# stm32-motor4.net
KiCad netlist of a schematic drawn in Altium Designer
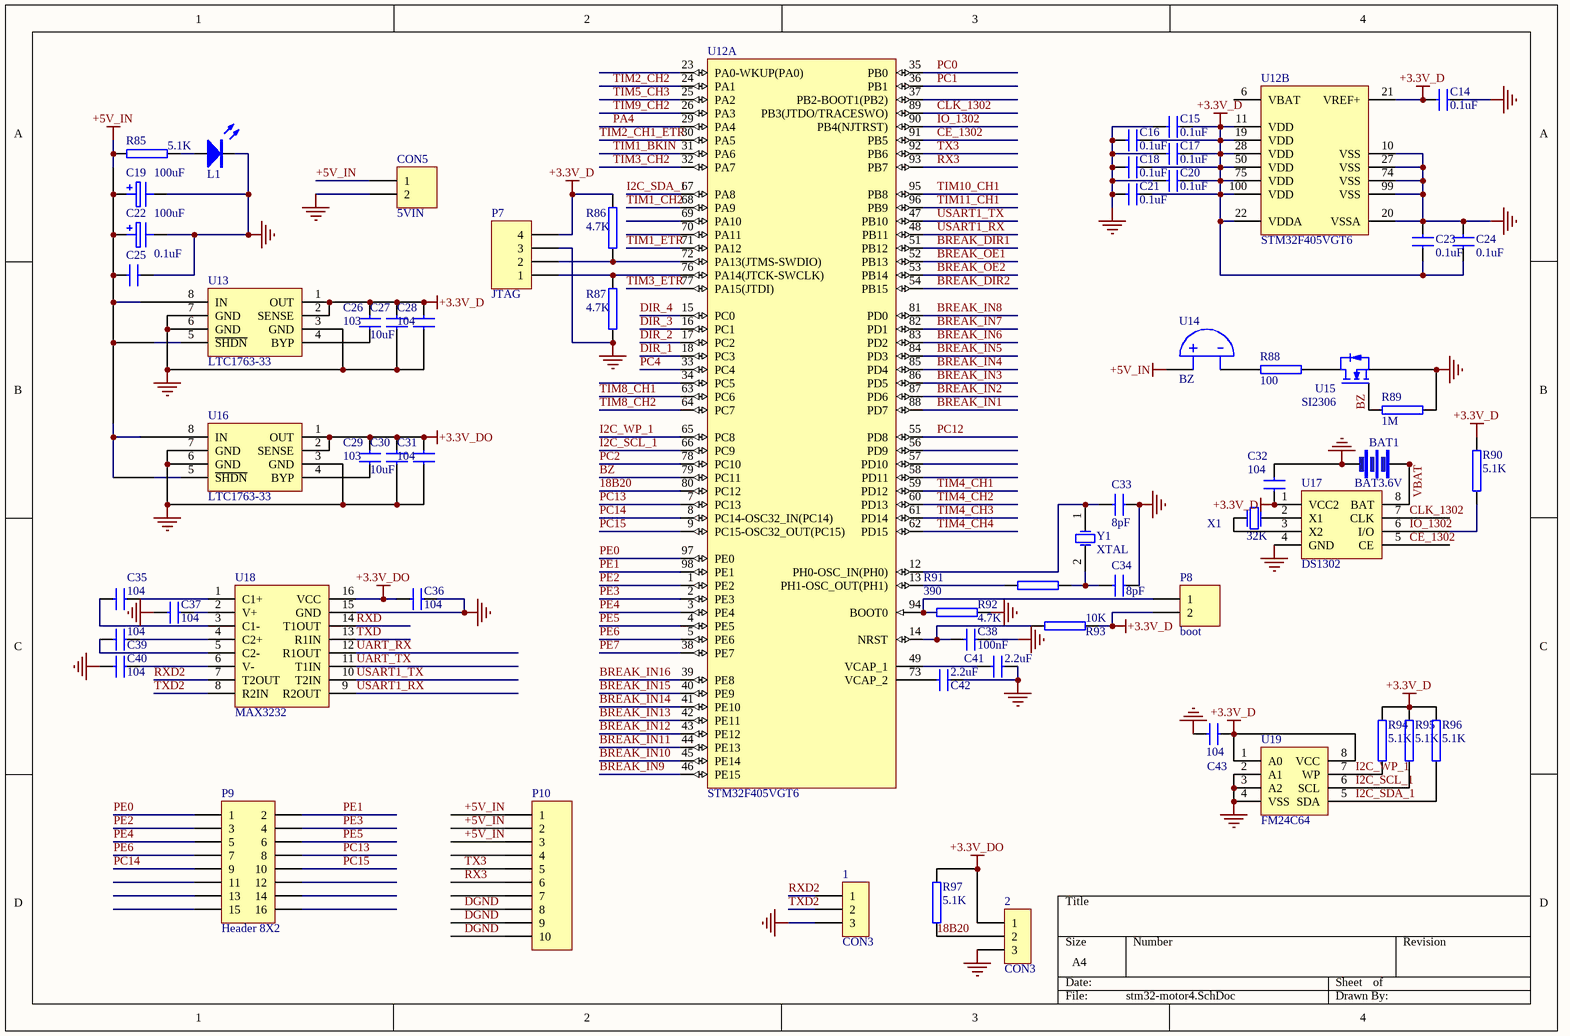
[diagram p0: stm32-motor4.SchDoc]

(export (version "E")
  (design (tool "Eeschema 10.0.6"))
  (components
    (comp (ref "1")
      (value "CON3")
      (footprint "SIP3")
      (description "Connector")
      (libsource (lib "插接件") (part "CON3"))
    )
    (comp (ref "2")
      (value "CON3")
      (footprint "SIP3")
      (description "Connector")
      (libsource (lib "插接件") (part "CON3"))
    )
    (comp (ref "BAT1") (value "BAT3.6V") (footprint "BAT") (libsource (lib "电池") (part "BAT3.6V")))
    (comp (ref "C14") (value "0.1uF") (footprint "0805") (libsource (lib "*") (part "C")))
    (comp (ref "C15") (value "0.1uF") (footprint "0805") (libsource (lib "*") (part "C")))
    (comp (ref "C16") (value "0.1uF") (footprint "0805") (libsource (lib "*") (part "C")))
    (comp (ref "C17") (value "0.1uF") (footprint "0805") (libsource (lib "*") (part "C")))
    (comp (ref "C18") (value "0.1uF") (footprint "0805") (libsource (lib "*") (part "C")))
    (comp (ref "C19") (value "100uF") (footprint "100UF/25V_CA") (libsource (lib "电容") (part "ELECTRO1")))
    (comp (ref "C20") (value "0.1uF") (footprint "0805") (libsource (lib "*") (part "C")))
    (comp (ref "C21") (value "0.1uF") (footprint "0805") (libsource (lib "*") (part "C")))
    (comp (ref "C22") (value "100uF") (footprint "100UF/25V_CA") (libsource (lib "电容") (part "ELECTRO1")))
    (comp (ref "C23") (value "0.1uF") (footprint "0805") (libsource (lib "*") (part "C")))
    (comp (ref "C24") (value "0.1uF") (footprint "0805") (libsource (lib "*") (part "C")))
    (comp (ref "C25") (value "0.1uF") (footprint "0805") (libsource (lib "电容") (part "C")))
    (comp (ref "C26") (value "103") (footprint "0603") (libsource (lib "电容") (part "C")))
    (comp (ref "C27") (value "10uF") (footprint "0805") (libsource (lib "电容") (part "C")))
    (comp (ref "C28") (value "104") (footprint "0805") (libsource (lib "电容") (part "C")))
    (comp (ref "C29") (value "103") (footprint "0603") (libsource (lib "电容") (part "C")))
    (comp (ref "C30") (value "10uF") (footprint "0805") (libsource (lib "电容") (part "C")))
    (comp (ref "C31") (value "104") (footprint "0805") (libsource (lib "电容") (part "C")))
    (comp (ref "C32") (value "104") (footprint "0805") (libsource (lib "电容") (part "C")))
    (comp (ref "C33") (value "8pF") (footprint "0805") (libsource (lib "*") (part "C")))
    (comp (ref "C34") (value "8pF") (footprint "0805") (libsource (lib "*") (part "C")))
    (comp (ref "C35") (value "104") (footprint "0805") (libsource (lib "*") (part "C")))
    (comp (ref "C36") (value "104") (footprint "0805") (libsource (lib "*") (part "C")))
    (comp (ref "C37") (value "104") (footprint "0805") (libsource (lib "*") (part "C")))
    (comp (ref "C38") (value "100nF") (footprint "0805") (libsource (lib "*") (part "C")))
    (comp (ref "C39") (value "104") (footprint "0805") (libsource (lib "*") (part "C")))
    (comp (ref "C40") (value "104") (footprint "0805") (libsource (lib "*") (part "C")))
    (comp (ref "C41") (value "2.2uF") (footprint "0805") (libsource (lib "*") (part "C")))
    (comp (ref "C42") (value "2.2uF") (footprint "0805") (libsource (lib "*") (part "C")))
    (comp (ref "C43") (value "104") (footprint "0805") (libsource (lib "电容") (part "C")))
    (comp (ref "CON5")
      (value "5VIN")
      (footprint "CON2")
      (description "Header, 2-Pin")
      (fields (field (name "PUBLISHER") "Altium Limited"))
      (libsource (lib "Miscellaneous Connectors") (part "Header 2"))
    )
    (comp (ref "L1") (value "LED") (footprint "0805LED") (libsource (lib "二极管") (part "LED")))
    (comp (ref "P7")
      (value "JTAG")
      (footprint "HDR1X4")
      (description "Header, 4-Pin")
      (fields (field (name "PUBLISHER") "Altium Limited"))
      (libsource (lib "Miscellaneous Connectors") (part "Header 4"))
    )
    (comp (ref "P8")
      (value "boot")
      (footprint "0603")
      (description "Header, 2-Pin")
      (fields (field (name "PUBLISHER") "Altium Limited"))
      (libsource (lib "Miscellaneous Connectors") (part "Header 2"))
    )
    (comp (ref "P9")
      (value "Header 8X2")
      (footprint "HDR2X8")
      (description "Header, 8-Pin, Dual row")
      (fields (field (name "PUBLISHER") "Altium Limited"))
      (libsource (lib "Miscellaneous Connectors") (part "Header 8X2"))
    )
    (comp (ref "P10")
      (value "ping")
      (footprint "PCBComponent_1")
      (description "Header, 10-Pin")
      (fields (field (name "PUBLISHER") "Altium Limited"))
      (libsource (lib "Miscellaneous Connectors") (part "Header 10"))
    )
    (comp (ref "R85") (value "5.1K") (footprint "0805") (libsource (lib "电阻") (part "RES")))
    (comp (ref "R86") (value "4.7K") (footprint "0805") (libsource (lib "*") (part "RES")))
    (comp (ref "R87") (value "4.7K") (footprint "0805") (libsource (lib "*") (part "RES")))
    (comp (ref "R88") (value "100") (footprint "0805") (libsource (lib "电阻") (part "RES")))
    (comp (ref "R89") (value "1M") (footprint "0805") (libsource (lib "电阻") (part "RES")))
    (comp (ref "R90") (value "5.1K") (footprint "0805") (libsource (lib "电阻") (part "RES")))
    (comp (ref "R91") (value "390") (footprint "0805") (libsource (lib "*") (part "RES")))
    (comp (ref "R92") (value "4.7K") (footprint "0805") (libsource (lib "*") (part "RES")))
    (comp (ref "R93") (value "10K") (footprint "0805") (libsource (lib "*") (part "RES")))
    (comp (ref "R94") (value "5.1K") (footprint "0805") (libsource (lib "电阻") (part "RES")))
    (comp (ref "R95") (value "5.1K") (footprint "0805") (libsource (lib "电阻") (part "RES")))
    (comp (ref "R96") (value "5.1K") (footprint "0805") (libsource (lib "电阻") (part "RES")))
    (comp (ref "R97") (value "5.1K") (footprint "0805") (libsource (lib "电阻") (part "RES")))
    (comp (ref "U12")
      (value "STM32F405VGT6")
      (footprint "STM-LQFP100_N")
      (fields (field (name "MANUFACTURER") "STMicroelectronics"))
      (libsource (lib "STMicroelectronics STM32 F4") (part "STM32F405VGT6"))
    )
    (comp (ref "U13") (value "LTC1763-33") (footprint "SO-8") (libsource (lib "单片机") (part "LT1763")))
    (comp (ref "U14") (value "BZ") (footprint "BZ_SMALL") (libsource (lib "蜂鸣器") (part "BZ")))
    (comp (ref "U15") (value "SI2306") (footprint "SOT-23") (libsource (lib "场效应管") (part "MOFET_N")))
    (comp (ref "U16") (value "LTC1763-33") (footprint "SO-8") (libsource (lib "单片机") (part "LT1763")))
    (comp (ref "U17") (value "DS1302") (footprint "SO-8") (libsource (lib "单片机") (part "DS1302")))
    (comp (ref "U18") (value "MAX3232") (footprint "SO-16") (libsource (lib "3D_GUASE") (part "MAX3232")))
    (comp (ref "U19") (value "FM24C64") (footprint "SO-8") (libsource (lib "单片机") (part "FM24C64")))
    (comp (ref "X1") (value "32K") (footprint "XTAL-2") (libsource (lib "晶振") (part "XTAL")))
    (comp (ref "Y1")
      (value "XTAL")
      (footprint "XTAL1")
      (description "Crystal Oscillator")
      (fields (field (name "PUBLISHER") "Altium Limited"))
      (libsource (lib "Miscellaneous Devices") (part "XTAL"))
    )
  )
  (nets
    (net (code "1") (name "+3.3V_D") (class "Default")
      (node (ref "C14") (pin "1") (pinfunction "1_1") (pintype "passive"))
      (node (ref "C15") (pin "2") (pinfunction "2_2") (pintype "passive"))
      (node (ref "C16") (pin "2") (pinfunction "2_2") (pintype "passive"))
      (node (ref "C17") (pin "2") (pinfunction "2_2") (pintype "passive"))
      (node (ref "C18") (pin "2") (pinfunction "2_2") (pintype "passive"))
      (node (ref "C20") (pin "2") (pinfunction "2_2") (pintype "passive"))
      (node (ref "C21") (pin "2") (pinfunction "2_2") (pintype "passive"))
      (node (ref "C23") (pin "2") (pinfunction "2_2") (pintype "passive"))
      (node (ref "C24") (pin "2") (pinfunction "2_2") (pintype "passive"))
      (node (ref "C26") (pin "1") (pinfunction "1_1") (pintype "passive"))
      (node (ref "C27") (pin "1") (pinfunction "1_1") (pintype "passive"))
      (node (ref "C28") (pin "1") (pinfunction "1_1") (pintype "passive"))
      (node (ref "C32") (pin "2") (pinfunction "2_2") (pintype "passive"))
      (node (ref "C43") (pin "1") (pinfunction "1_1") (pintype "passive"))
      (node (ref "P7") (pin "4") (pinfunction "4_4") (pintype "passive"))
      (node (ref "P8") (pin "2") (pinfunction "2_2") (pintype "passive"))
      (node (ref "R86") (pin "1") (pinfunction "1_1") (pintype "passive"))
      (node (ref "R90") (pin "2") (pinfunction "2_2") (pintype "passive"))
      (node (ref "R93") (pin "2") (pinfunction "2_2") (pintype "passive"))
      (node (ref "R94") (pin "2") (pinfunction "2_2") (pintype "passive"))
      (node (ref "R95") (pin "2") (pinfunction "2_2") (pintype "passive"))
      (node (ref "R96") (pin "2") (pinfunction "2_2") (pintype "passive"))
      (node (ref "U12") (pin "100") (pinfunction "VDD_100") (pintype "power_in"))
      (node (ref "U12") (pin "11") (pinfunction "VDD_11") (pintype "power_in"))
      (node (ref "U12") (pin "19") (pinfunction "VDD_19") (pintype "power_in"))
      (node (ref "U12") (pin "21") (pinfunction "VREF+_21") (pintype "power_in"))
      (node (ref "U12") (pin "22") (pinfunction "VDDA_22") (pintype "power_in"))
      (node (ref "U12") (pin "28") (pinfunction "VDD_28") (pintype "power_in"))
      (node (ref "U12") (pin "50") (pinfunction "VDD_50") (pintype "power_in"))
      (node (ref "U12") (pin "75") (pinfunction "VDD_75") (pintype "power_in"))
      (node (ref "U13") (pin "1") (pinfunction "OUT_1") (pintype "passive"))
      (node (ref "U13") (pin "2") (pinfunction "SENSE_2") (pintype "passive"))
      (node (ref "U17") (pin "1") (pinfunction "VCC2_1") (pintype "passive"))
      (node (ref "U19") (pin "1") (pinfunction "A0_1") (pintype "passive"))
      (node (ref "U19") (pin "8") (pinfunction "VCC_8") (pintype "passive"))
    )
    (net (code "2") (name "+3.3V_DO") (class "Default")
      (node (ref "2") (pin "1") (pinfunction "1_1") (pintype "passive"))
      (node (ref "C29") (pin "1") (pinfunction "1_1") (pintype "passive"))
      (node (ref "C30") (pin "1") (pinfunction "1_1") (pintype "passive"))
      (node (ref "C31") (pin "1") (pinfunction "1_1") (pintype "passive"))
      (node (ref "C36") (pin "1") (pinfunction "1_1") (pintype "passive"))
      (node (ref "R97") (pin "2") (pinfunction "2_2") (pintype "passive"))
      (node (ref "U16") (pin "1") (pinfunction "OUT_1") (pintype "passive"))
      (node (ref "U16") (pin "2") (pinfunction "SENSE_2") (pintype "passive"))
      (node (ref "U18") (pin "16") (pinfunction "VCC_16") (pintype "passive"))
    )
    (net (code "3") (name "+5V_IN") (class "Default")
      (node (ref "C19") (pin "1") (pintype "passive"))
      (node (ref "C22") (pin "1") (pintype "passive"))
      (node (ref "C25") (pin "1") (pinfunction "1_1") (pintype "passive"))
      (node (ref "CON5") (pin "1") (pinfunction "1_1") (pintype "passive"))
      (node (ref "P10") (pin "1") (pinfunction "1_1") (pintype "passive"))
      (node (ref "P10") (pin "2") (pinfunction "2_2") (pintype "passive"))
      (node (ref "P10") (pin "3") (pinfunction "3_3") (pintype "passive"))
      (node (ref "R85") (pin "2") (pinfunction "2_2") (pintype "passive"))
      (node (ref "U13") (pin "5") (pinfunction "~{SHDN}_5") (pintype "passive"))
      (node (ref "U13") (pin "8") (pinfunction "IN_8") (pintype "passive"))
      (node (ref "U14") (pin "1") (pintype "passive"))
      (node (ref "U16") (pin "5") (pinfunction "~{SHDN}_5") (pintype "passive"))
      (node (ref "U16") (pin "8") (pinfunction "IN_8") (pintype "passive"))
    )
    (net (code "4") (name "/18B20") (class "Default")
      (node (ref "2") (pin "2") (pinfunction "2_2") (pintype "passive"))
      (node (ref "R97") (pin "1") (pinfunction "1_1") (pintype "passive"))
      (node (ref "U12") (pin "80") (pinfunction "PC12_80") (pintype "bidirectional"))
    )
    (net (code "5") (name "/BREAK_DIR1") (class "Default")
      (node (ref "U12") (pin "51") (pinfunction "PB12_51") (pintype "bidirectional"))
    )
    (net (code "6") (name "/BREAK_DIR2") (class "Default")
      (node (ref "U12") (pin "54") (pinfunction "PB15_54") (pintype "bidirectional"))
    )
    (net (code "7") (name "/BREAK_IN1") (class "Default")
      (node (ref "U12") (pin "88") (pinfunction "PD7_88") (pintype "bidirectional"))
    )
    (net (code "8") (name "/BREAK_IN2") (class "Default")
      (node (ref "U12") (pin "87") (pinfunction "PD6_87") (pintype "bidirectional"))
    )
    (net (code "9") (name "/BREAK_IN3") (class "Default")
      (node (ref "U12") (pin "86") (pinfunction "PD5_86") (pintype "bidirectional"))
    )
    (net (code "10") (name "/BREAK_IN4") (class "Default")
      (node (ref "U12") (pin "85") (pinfunction "PD4_85") (pintype "bidirectional"))
    )
    (net (code "11") (name "/BREAK_IN5") (class "Default")
      (node (ref "U12") (pin "84") (pinfunction "PD3_84") (pintype "bidirectional"))
    )
    (net (code "12") (name "/BREAK_IN6") (class "Default")
      (node (ref "U12") (pin "83") (pinfunction "PD2_83") (pintype "bidirectional"))
    )
    (net (code "13") (name "/BREAK_IN7") (class "Default")
      (node (ref "U12") (pin "82") (pinfunction "PD1_82") (pintype "bidirectional"))
    )
    (net (code "14") (name "/BREAK_IN8") (class "Default")
      (node (ref "U12") (pin "81") (pinfunction "PD0_81") (pintype "bidirectional"))
    )
    (net (code "15") (name "/BREAK_IN9") (class "Default")
      (node (ref "U12") (pin "46") (pinfunction "PE15_46") (pintype "bidirectional"))
    )
    (net (code "16") (name "/BREAK_IN10") (class "Default")
      (node (ref "U12") (pin "45") (pinfunction "PE14_45") (pintype "bidirectional"))
    )
    (net (code "17") (name "/BREAK_IN11") (class "Default")
      (node (ref "U12") (pin "44") (pinfunction "PE13_44") (pintype "bidirectional"))
    )
    (net (code "18") (name "/BREAK_IN12") (class "Default")
      (node (ref "U12") (pin "43") (pinfunction "PE12_43") (pintype "bidirectional"))
    )
    (net (code "19") (name "/BREAK_IN13") (class "Default")
      (node (ref "U12") (pin "42") (pinfunction "PE11_42") (pintype "bidirectional"))
    )
    (net (code "20") (name "/BREAK_IN14") (class "Default")
      (node (ref "U12") (pin "41") (pinfunction "PE10_41") (pintype "bidirectional"))
    )
    (net (code "21") (name "/BREAK_IN15") (class "Default")
      (node (ref "U12") (pin "40") (pinfunction "PE9_40") (pintype "bidirectional"))
    )
    (net (code "22") (name "/BREAK_IN16") (class "Default")
      (node (ref "U12") (pin "39") (pinfunction "PE8_39") (pintype "bidirectional"))
    )
    (net (code "23") (name "/BREAK_OE1") (class "Default")
      (node (ref "U12") (pin "52") (pinfunction "PB13_52") (pintype "bidirectional"))
    )
    (net (code "24") (name "/BREAK_OE2") (class "Default")
      (node (ref "U12") (pin "53") (pinfunction "PB14_53") (pintype "bidirectional"))
    )
    (net (code "25") (name "/BZ") (class "Default")
      (node (ref "R89") (pin "2") (pinfunction "2_2") (pintype "passive"))
      (node (ref "U12") (pin "79") (pinfunction "PC11_79") (pintype "bidirectional"))
      (node (ref "U15") (pin "B") (pinfunction "B_B") (pintype "passive"))
    )
    (net (code "26") (name "/CE_1302") (class "Default")
      (node (ref "U12") (pin "91") (pinfunction "PB5_91") (pintype "bidirectional"))
      (node (ref "U17") (pin "5") (pinfunction "CE_5") (pintype "passive"))
    )
    (net (code "27") (name "/CLK_1302") (class "Default")
      (node (ref "U12") (pin "89") (pinfunction "PB3(JTDO/TRACESWO)_89") (pintype "bidirectional"))
      (node (ref "U17") (pin "7") (pinfunction "CLK_7") (pintype "passive"))
    )
    (net (code "28") (name "/DIR_1") (class "Default")
      (node (ref "U12") (pin "18") (pinfunction "PC3_18") (pintype "bidirectional"))
    )
    (net (code "29") (name "/DIR_2") (class "Default")
      (node (ref "U12") (pin "17") (pinfunction "PC2_17") (pintype "bidirectional"))
    )
    (net (code "30") (name "/DIR_3") (class "Default")
      (node (ref "U12") (pin "16") (pinfunction "PC1_16") (pintype "bidirectional"))
    )
    (net (code "31") (name "/DIR_4") (class "Default")
      (node (ref "U12") (pin "15") (pinfunction "PC0_15") (pintype "bidirectional"))
    )
    (net (code "32") (name "/I2C_SCL_1") (class "Default")
      (node (ref "R95") (pin "1") (pinfunction "1_1") (pintype "passive"))
      (node (ref "U12") (pin "66") (pinfunction "PC9_66") (pintype "bidirectional"))
      (node (ref "U19") (pin "6") (pinfunction "SCL_6") (pintype "passive"))
    )
    (net (code "33") (name "/I2C_SDA_1") (class "Default")
      (node (ref "R96") (pin "1") (pinfunction "1_1") (pintype "passive"))
      (node (ref "U12") (pin "67") (pinfunction "PA8_67") (pintype "bidirectional"))
      (node (ref "U19") (pin "5") (pinfunction "SDA_5") (pintype "passive"))
    )
    (net (code "34") (name "/I2C_WP_1") (class "Default")
      (node (ref "R94") (pin "1") (pinfunction "1_1") (pintype "passive"))
      (node (ref "U12") (pin "65") (pinfunction "PC8_65") (pintype "bidirectional"))
      (node (ref "U19") (pin "7") (pinfunction "WP_7") (pintype "passive"))
    )
    (net (code "35") (name "/IO_1302") (class "Default")
      (node (ref "R90") (pin "1") (pinfunction "1_1") (pintype "passive"))
      (node (ref "U12") (pin "90") (pinfunction "PB4(NJTRST)_90") (pintype "bidirectional"))
      (node (ref "U17") (pin "6") (pinfunction "I/O_6") (pintype "passive"))
    )
    (net (code "36") (name "/PA4") (class "Default")
      (node (ref "U12") (pin "29") (pinfunction "PA4_29") (pintype "bidirectional"))
    )
    (net (code "37") (name "/PC0") (class "Default")
      (node (ref "U12") (pin "35") (pinfunction "PB0_35") (pintype "bidirectional"))
    )
    (net (code "38") (name "/PC1") (class "Default")
      (node (ref "U12") (pin "36") (pinfunction "PB1_36") (pintype "bidirectional"))
    )
    (net (code "39") (name "/PC2") (class "Default")
      (node (ref "U12") (pin "78") (pinfunction "PC10_78") (pintype "bidirectional"))
    )
    (net (code "40") (name "/PC4") (class "Default")
      (node (ref "U12") (pin "33") (pinfunction "PC4_33") (pintype "bidirectional"))
    )
    (net (code "41") (name "/PC12") (class "Default")
      (node (ref "U12") (pin "55") (pinfunction "PD8_55") (pintype "bidirectional"))
    )
    (net (code "42") (name "/PC13") (class "Default")
      (node (ref "P9") (pin "8") (pinfunction "8_8") (pintype "passive"))
      (node (ref "U12") (pin "7") (pinfunction "PC13_7") (pintype "bidirectional"))
    )
    (net (code "43") (name "/PC14") (class "Default")
      (node (ref "P9") (pin "9") (pinfunction "9_9") (pintype "passive"))
      (node (ref "U12") (pin "8") (pinfunction "PC14-OSC32_IN(PC14)_8") (pintype "bidirectional"))
    )
    (net (code "44") (name "/PC15") (class "Default")
      (node (ref "P9") (pin "10") (pinfunction "10_10") (pintype "passive"))
      (node (ref "U12") (pin "9") (pinfunction "PC15-OSC32_OUT(PC15)_9") (pintype "bidirectional"))
    )
    (net (code "45") (name "/PE0") (class "Default")
      (node (ref "P9") (pin "1") (pinfunction "1_1") (pintype "passive"))
      (node (ref "U12") (pin "97") (pinfunction "PE0_97") (pintype "bidirectional"))
    )
    (net (code "46") (name "/PE1") (class "Default")
      (node (ref "P9") (pin "2") (pinfunction "2_2") (pintype "passive"))
      (node (ref "U12") (pin "98") (pinfunction "PE1_98") (pintype "bidirectional"))
    )
    (net (code "47") (name "/PE2") (class "Default")
      (node (ref "P9") (pin "3") (pinfunction "3_3") (pintype "passive"))
      (node (ref "U12") (pin "1") (pinfunction "PE2_1") (pintype "bidirectional"))
    )
    (net (code "48") (name "/PE3") (class "Default")
      (node (ref "P9") (pin "4") (pinfunction "4_4") (pintype "passive"))
      (node (ref "U12") (pin "2") (pinfunction "PE3_2") (pintype "bidirectional"))
    )
    (net (code "49") (name "/PE4") (class "Default")
      (node (ref "P9") (pin "5") (pinfunction "5_5") (pintype "passive"))
      (node (ref "U12") (pin "3") (pinfunction "PE4_3") (pintype "bidirectional"))
    )
    (net (code "50") (name "/PE5") (class "Default")
      (node (ref "P9") (pin "6") (pinfunction "6_6") (pintype "passive"))
      (node (ref "U12") (pin "4") (pinfunction "PE5_4") (pintype "bidirectional"))
    )
    (net (code "51") (name "/PE6") (class "Default")
      (node (ref "P9") (pin "7") (pinfunction "7_7") (pintype "passive"))
      (node (ref "U12") (pin "5") (pinfunction "PE6_5") (pintype "bidirectional"))
    )
    (net (code "52") (name "/PE7") (class "Default")
      (node (ref "U12") (pin "38") (pinfunction "PE7_38") (pintype "bidirectional"))
    )
    (net (code "53") (name "/RX3") (class "Default")
      (node (ref "P10") (pin "6") (pinfunction "6_6") (pintype "passive"))
      (node (ref "U12") (pin "93") (pinfunction "PB7_93") (pintype "bidirectional"))
    )
    (net (code "54") (name "/RXD") (class "Default")
      (node (ref "U18") (pin "14") (pinfunction "T1OUT_14") (pintype "passive"))
    )
    (net (code "55") (name "/RXD2") (class "Default")
      (node (ref "1") (pin "1") (pinfunction "1_1") (pintype "passive"))
      (node (ref "U18") (pin "7") (pinfunction "T2OUT_7") (pintype "passive"))
    )
    (net (code "56") (name "/TIM1_BKIN") (class "Default")
      (node (ref "U12") (pin "31") (pinfunction "PA6_31") (pintype "bidirectional"))
    )
    (net (code "57") (name "/TIM1_CH2") (class "Default")
      (node (ref "U12") (pin "68") (pinfunction "PA9_68") (pintype "bidirectional"))
    )
    (net (code "58") (name "/TIM1_ETR") (class "Default")
      (node (ref "U12") (pin "71") (pinfunction "PA12_71") (pintype "bidirectional"))
    )
    (net (code "59") (name "/TIM2_CH1_ETR") (class "Default")
      (node (ref "U12") (pin "30") (pinfunction "PA5_30") (pintype "bidirectional"))
    )
    (net (code "60") (name "/TIM2_CH2") (class "Default")
      (node (ref "U12") (pin "24") (pinfunction "PA1_24") (pintype "bidirectional"))
    )
    (net (code "61") (name "/TIM3_CH2") (class "Default")
      (node (ref "U12") (pin "32") (pinfunction "PA7_32") (pintype "bidirectional"))
    )
    (net (code "62") (name "/TIM3_ETR") (class "Default")
      (node (ref "U12") (pin "77") (pinfunction "PA15(JTDI)_77") (pintype "bidirectional"))
    )
    (net (code "63") (name "/TIM4_CH1") (class "Default")
      (node (ref "U12") (pin "59") (pinfunction "PD12_59") (pintype "bidirectional"))
    )
    (net (code "64") (name "/TIM4_CH2") (class "Default")
      (node (ref "U12") (pin "60") (pinfunction "PD13_60") (pintype "bidirectional"))
    )
    (net (code "65") (name "/TIM4_CH3") (class "Default")
      (node (ref "U12") (pin "61") (pinfunction "PD14_61") (pintype "bidirectional"))
    )
    (net (code "66") (name "/TIM4_CH4") (class "Default")
      (node (ref "U12") (pin "62") (pinfunction "PD15_62") (pintype "bidirectional"))
    )
    (net (code "67") (name "/TIM5_CH3") (class "Default")
      (node (ref "U12") (pin "25") (pinfunction "PA2_25") (pintype "bidirectional"))
    )
    (net (code "68") (name "/TIM8_CH1") (class "Default")
      (node (ref "U12") (pin "63") (pinfunction "PC6_63") (pintype "bidirectional"))
    )
    (net (code "69") (name "/TIM8_CH2") (class "Default")
      (node (ref "U12") (pin "64") (pinfunction "PC7_64") (pintype "bidirectional"))
    )
    (net (code "70") (name "/TIM9_CH2") (class "Default")
      (node (ref "U12") (pin "26") (pinfunction "PA3_26") (pintype "bidirectional"))
    )
    (net (code "71") (name "/TIM10_CH1") (class "Default")
      (node (ref "U12") (pin "95") (pinfunction "PB8_95") (pintype "bidirectional"))
    )
    (net (code "72") (name "/TIM11_CH1") (class "Default")
      (node (ref "U12") (pin "96") (pinfunction "PB9_96") (pintype "bidirectional"))
    )
    (net (code "73") (name "/TX3") (class "Default")
      (node (ref "P10") (pin "5") (pinfunction "5_5") (pintype "passive"))
      (node (ref "U12") (pin "92") (pinfunction "PB6_92") (pintype "bidirectional"))
    )
    (net (code "74") (name "/TXD") (class "Default")
      (node (ref "U18") (pin "13") (pinfunction "R1IN_13") (pintype "passive"))
    )
    (net (code "75") (name "/TXD2") (class "Default")
      (node (ref "1") (pin "2") (pinfunction "2_2") (pintype "passive"))
      (node (ref "U18") (pin "8") (pinfunction "R2IN_8") (pintype "passive"))
    )
    (net (code "76") (name "/UART_RX") (class "Default")
      (node (ref "U18") (pin "12") (pinfunction "R1OUT_12") (pintype "passive"))
    )
    (net (code "77") (name "/UART_TX") (class "Default")
      (node (ref "U18") (pin "11") (pinfunction "T1IN_11") (pintype "passive"))
    )
    (net (code "78") (name "/USART1_RX") (class "Default")
      (node (ref "U12") (pin "48") (pinfunction "PB11_48") (pintype "bidirectional"))
      (node (ref "U18") (pin "9") (pinfunction "R2OUT_9") (pintype "passive"))
    )
    (net (code "79") (name "/USART1_TX") (class "Default")
      (node (ref "U12") (pin "47") (pinfunction "PB10_47") (pintype "bidirectional"))
      (node (ref "U18") (pin "10") (pinfunction "T2IN_10") (pintype "passive"))
    )
    (net (code "80") (name "/VBAT") (class "Default")
      (node (ref "BAT1") (pin "1") (pinfunction "1_1") (pintype "passive"))
      (node (ref "U17") (pin "8") (pinfunction "BAT_8") (pintype "passive"))
    )
    (net (code "81") (name "DGND") (class "Default")
      (node (ref "1") (pin "3") (pinfunction "3_3") (pintype "passive"))
      (node (ref "2") (pin "3") (pinfunction "3_3") (pintype "passive"))
      (node (ref "BAT1") (pin "2") (pinfunction "2_2") (pintype "passive"))
      (node (ref "C14") (pin "2") (pinfunction "2_2") (pintype "passive"))
      (node (ref "C15") (pin "1") (pinfunction "1_1") (pintype "passive"))
      (node (ref "C16") (pin "1") (pinfunction "1_1") (pintype "passive"))
      (node (ref "C17") (pin "1") (pinfunction "1_1") (pintype "passive"))
      (node (ref "C18") (pin "1") (pinfunction "1_1") (pintype "passive"))
      (node (ref "C19") (pin "2") (pintype "passive"))
      (node (ref "C20") (pin "1") (pinfunction "1_1") (pintype "passive"))
      (node (ref "C21") (pin "1") (pinfunction "1_1") (pintype "passive"))
      (node (ref "C22") (pin "2") (pintype "passive"))
      (node (ref "C23") (pin "1") (pinfunction "1_1") (pintype "passive"))
      (node (ref "C24") (pin "1") (pinfunction "1_1") (pintype "passive"))
      (node (ref "C25") (pin "2") (pinfunction "2_2") (pintype "passive"))
      (node (ref "C27") (pin "2") (pinfunction "2_2") (pintype "passive"))
      (node (ref "C28") (pin "2") (pinfunction "2_2") (pintype "passive"))
      (node (ref "C30") (pin "2") (pinfunction "2_2") (pintype "passive"))
      (node (ref "C31") (pin "2") (pinfunction "2_2") (pintype "passive"))
      (node (ref "C32") (pin "1") (pinfunction "1_1") (pintype "passive"))
      (node (ref "C33") (pin "2") (pinfunction "2_2") (pintype "passive"))
      (node (ref "C34") (pin "2") (pinfunction "2_2") (pintype "passive"))
      (node (ref "C36") (pin "2") (pinfunction "2_2") (pintype "passive"))
      (node (ref "C37") (pin "1") (pinfunction "1_1") (pintype "passive"))
      (node (ref "C38") (pin "2") (pinfunction "2_2") (pintype "passive"))
      (node (ref "C40") (pin "1") (pinfunction "1_1") (pintype "passive"))
      (node (ref "C41") (pin "2") (pinfunction "2_2") (pintype "passive"))
      (node (ref "C42") (pin "2") (pinfunction "2_2") (pintype "passive"))
      (node (ref "C43") (pin "2") (pinfunction "2_2") (pintype "passive"))
      (node (ref "CON5") (pin "2") (pinfunction "2_2") (pintype "passive"))
      (node (ref "L1") (pin "2") (pinfunction "K_2") (pintype "passive"))
      (node (ref "P10") (pin "10") (pinfunction "10_10") (pintype "passive"))
      (node (ref "P10") (pin "8") (pinfunction "8_8") (pintype "passive"))
      (node (ref "P10") (pin "9") (pinfunction "9_9") (pintype "passive"))
      (node (ref "P7") (pin "3") (pinfunction "3_3") (pintype "passive"))
      (node (ref "R87") (pin "2") (pinfunction "2_2") (pintype "passive"))
      (node (ref "R89") (pin "1") (pinfunction "1_1") (pintype "passive"))
      (node (ref "R92") (pin "1") (pinfunction "1_1") (pintype "passive"))
      (node (ref "U12") (pin "10") (pinfunction "VSS_10") (pintype "power_in"))
      (node (ref "U12") (pin "20") (pinfunction "VSSA_20") (pintype "power_in"))
      (node (ref "U12") (pin "27") (pinfunction "VSS_27") (pintype "power_in"))
      (node (ref "U12") (pin "74") (pinfunction "VSS_74") (pintype "power_in"))
      (node (ref "U12") (pin "99") (pinfunction "VSS_99") (pintype "power_in"))
      (node (ref "U13") (pin "3") (pinfunction "GND_3") (pintype "passive"))
      (node (ref "U13") (pin "6") (pinfunction "GND_6") (pintype "passive"))
      (node (ref "U13") (pin "7") (pinfunction "GND_7") (pintype "passive"))
      (node (ref "U15") (pin "E") (pinfunction "E_E") (pintype "passive"))
      (node (ref "U16") (pin "3") (pinfunction "GND_3") (pintype "passive"))
      (node (ref "U16") (pin "6") (pinfunction "GND_6") (pintype "passive"))
      (node (ref "U16") (pin "7") (pinfunction "GND_7") (pintype "passive"))
      (node (ref "U17") (pin "4") (pinfunction "GND_4") (pintype "passive"))
      (node (ref "U18") (pin "15") (pinfunction "GND_15") (pintype "passive"))
      (node (ref "U19") (pin "2") (pinfunction "A1_2") (pintype "passive"))
      (node (ref "U19") (pin "3") (pinfunction "A2_3") (pintype "passive"))
      (node (ref "U19") (pin "4") (pinfunction "VSS_4") (pintype "passive"))
    )
    (net (code "82") (name "Net-(L1-A)") (class "Default")
      (node (ref "L1") (pin "1") (pinfunction "A_1") (pintype "passive"))
      (node (ref "R85") (pin "1") (pinfunction "1_1") (pintype "passive"))
    )
    (net (code "83") (name "Net-(R88-Pad1)") (class "Default")
      (node (ref "R88") (pin "1") (pinfunction "1_1") (pintype "passive"))
      (node (ref "U15") (pin "C") (pinfunction "C_C") (pintype "passive"))
    )
    (net (code "84") (name "Net-(R88-Pad2)") (class "Default")
      (node (ref "R88") (pin "2") (pinfunction "2_2") (pintype "passive"))
      (node (ref "U14") (pin "2") (pintype "passive"))
    )
    (net (code "85") (name "Net-(U12A-BOOT0)") (class "Default")
      (node (ref "P8") (pin "1") (pinfunction "1_1") (pintype "passive"))
      (node (ref "R92") (pin "2") (pinfunction "2_2") (pintype "passive"))
      (node (ref "U12") (pin "94") (pinfunction "BOOT0_94") (pintype "input"))
    )
    (net (code "86") (name "Net-(U12A-NRST)") (class "Default")
      (node (ref "C38") (pin "1") (pinfunction "1_1") (pintype "passive"))
      (node (ref "R93") (pin "1") (pinfunction "1_1") (pintype "passive"))
      (node (ref "U12") (pin "14") (pinfunction "NRST_14") (pintype "bidirectional"))
    )
    (net (code "87") (name "Net-(U12A-PA13(JTMS-SWDIO))") (class "Default")
      (node (ref "P7") (pin "2") (pinfunction "2_2") (pintype "passive"))
      (node (ref "R86") (pin "2") (pinfunction "2_2") (pintype "passive"))
      (node (ref "U12") (pin "72") (pinfunction "PA13(JTMS-SWDIO)_72") (pintype "bidirectional"))
    )
    (net (code "88") (name "Net-(U12A-PA14(JTCK-SWCLK))") (class "Default")
      (node (ref "P7") (pin "1") (pinfunction "1_1") (pintype "passive"))
      (node (ref "R87") (pin "1") (pinfunction "1_1") (pintype "passive"))
      (node (ref "U12") (pin "76") (pinfunction "PA14(JTCK-SWCLK)_76") (pintype "bidirectional"))
    )
    (net (code "89") (name "Net-(U12A-PH0-OSC_IN(PH0))") (class "Default")
      (node (ref "C33") (pin "1") (pinfunction "1_1") (pintype "passive"))
      (node (ref "U12") (pin "12") (pinfunction "PH0-OSC_IN(PH0)_12") (pintype "bidirectional"))
      (node (ref "Y1") (pin "1") (pinfunction "OSC1_1") (pintype "passive"))
    )
    (net (code "90") (name "Net-(U12A-PH1-OSC_OUT(PH1))") (class "Default")
      (node (ref "R91") (pin "1") (pinfunction "1_1") (pintype "passive"))
      (node (ref "U12") (pin "13") (pinfunction "PH1-OSC_OUT(PH1)_13") (pintype "bidirectional"))
    )
    (net (code "91") (name "Net-(U12A-VCAP_1)") (class "Default")
      (node (ref "C41") (pin "1") (pinfunction "1_1") (pintype "passive"))
      (node (ref "U12") (pin "49") (pinfunction "VCAP_1_49") (pintype "power_in"))
    )
    (net (code "92") (name "Net-(U12A-VCAP_2)") (class "Default")
      (node (ref "C42") (pin "1") (pinfunction "1_1") (pintype "passive"))
      (node (ref "U12") (pin "73") (pinfunction "VCAP_2_73") (pintype "power_in"))
    )
    (net (code "93") (name "Net-(U13-BYP)") (class "Default")
      (node (ref "C26") (pin "2") (pinfunction "2_2") (pintype "passive"))
      (node (ref "U13") (pin "4") (pinfunction "BYP_4") (pintype "passive"))
    )
    (net (code "94") (name "Net-(U16-BYP)") (class "Default")
      (node (ref "C29") (pin "2") (pinfunction "2_2") (pintype "passive"))
      (node (ref "U16") (pin "4") (pinfunction "BYP_4") (pintype "passive"))
    )
    (net (code "95") (name "Net-(U17-X1)") (class "Default")
      (node (ref "U17") (pin "2") (pinfunction "X1_2") (pintype "passive"))
      (node (ref "X1") (pin "2") (pinfunction "P2_2") (pintype "passive"))
    )
    (net (code "96") (name "Net-(U17-X2)") (class "Default")
      (node (ref "U17") (pin "3") (pinfunction "X2_3") (pintype "passive"))
      (node (ref "X1") (pin "1") (pinfunction "P1_1") (pintype "passive"))
    )
    (net (code "97") (name "Net-(U18-C1+)") (class "Default")
      (node (ref "C35") (pin "2") (pinfunction "2_2") (pintype "passive"))
      (node (ref "U18") (pin "1") (pinfunction "C1+_1") (pintype "passive"))
    )
    (net (code "98") (name "Net-(U18-C1-)") (class "Default")
      (node (ref "C35") (pin "1") (pinfunction "1_1") (pintype "passive"))
      (node (ref "U18") (pin "3") (pinfunction "C1-_3") (pintype "passive"))
    )
    (net (code "99") (name "Net-(U18-C2+)") (class "Default")
      (node (ref "C39") (pin "2") (pinfunction "2_2") (pintype "passive"))
      (node (ref "U18") (pin "4") (pinfunction "C2+_4") (pintype "passive"))
    )
    (net (code "100") (name "Net-(U18-C2-)") (class "Default")
      (node (ref "C39") (pin "1") (pinfunction "1_1") (pintype "passive"))
      (node (ref "U18") (pin "5") (pinfunction "C2-_5") (pintype "passive"))
    )
    (net (code "101") (name "Net-(U18-V+)") (class "Default")
      (node (ref "C37") (pin "2") (pinfunction "2_2") (pintype "passive"))
      (node (ref "U18") (pin "2") (pinfunction "V+_2") (pintype "passive"))
    )
    (net (code "102") (name "Net-(U18-V-)") (class "Default")
      (node (ref "C40") (pin "2") (pinfunction "2_2") (pintype "passive"))
      (node (ref "U18") (pin "6") (pinfunction "V-_6") (pintype "passive"))
    )
    (net (code "103") (name "Net-(Y1-OSC2)") (class "Default")
      (node (ref "C34") (pin "1") (pinfunction "1_1") (pintype "passive"))
      (node (ref "R91") (pin "2") (pinfunction "2_2") (pintype "passive"))
      (node (ref "Y1") (pin "2") (pinfunction "OSC2_2") (pintype "passive"))
    )
    (net (code "104") (name "unconnected-(P9-Pad11)") (class "Default")
      (node (ref "P9") (pin "11") (pinfunction "11_11") (pintype "passive"))
    )
    (net (code "105") (name "unconnected-(P9-Pad12)") (class "Default")
      (node (ref "P9") (pin "12") (pinfunction "12_12") (pintype "passive"))
    )
    (net (code "106") (name "unconnected-(P9-Pad13)") (class "Default")
      (node (ref "P9") (pin "13") (pinfunction "13_13") (pintype "passive"))
    )
    (net (code "107") (name "unconnected-(P9-Pad14)") (class "Default")
      (node (ref "P9") (pin "14") (pinfunction "14_14") (pintype "passive"))
    )
    (net (code "108") (name "unconnected-(P9-Pad15)") (class "Default")
      (node (ref "P9") (pin "15") (pinfunction "15_15") (pintype "passive"))
    )
    (net (code "109") (name "unconnected-(P9-Pad16)") (class "Default")
      (node (ref "P9") (pin "16") (pinfunction "16_16") (pintype "passive"))
    )
    (net (code "110") (name "unconnected-(P10-Pad4)") (class "Default")
      (node (ref "P10") (pin "4") (pinfunction "4_4") (pintype "passive"))
    )
    (net (code "111") (name "unconnected-(P10-Pad7)") (class "Default")
      (node (ref "P10") (pin "7") (pinfunction "7_7") (pintype "passive"))
    )
    (net (code "112") (name "unconnected-(U12A-PA0-WKUP(PA0)-Pad23)") (class "Default")
      (node (ref "U12") (pin "23") (pinfunction "PA0-WKUP(PA0)_23") (pintype "bidirectional"))
    )
    (net (code "113") (name "unconnected-(U12A-PA10-Pad69)") (class "Default")
      (node (ref "U12") (pin "69") (pinfunction "PA10_69") (pintype "bidirectional"))
    )
    (net (code "114") (name "unconnected-(U12A-PA11-Pad70)") (class "Default")
      (node (ref "U12") (pin "70") (pinfunction "PA11_70") (pintype "bidirectional"))
    )
    (net (code "115") (name "unconnected-(U12A-PB2-BOOT1(PB2)-Pad37)") (class "Default")
      (node (ref "U12") (pin "37") (pinfunction "PB2-BOOT1(PB2)_37") (pintype "bidirectional"))
    )
    (net (code "116") (name "unconnected-(U12A-PC5-Pad34)") (class "Default")
      (node (ref "U12") (pin "34") (pinfunction "PC5_34") (pintype "bidirectional"))
    )
    (net (code "117") (name "unconnected-(U12A-PD9-Pad56)") (class "Default")
      (node (ref "U12") (pin "56") (pinfunction "PD9_56") (pintype "bidirectional"))
    )
    (net (code "118") (name "unconnected-(U12A-PD10-Pad57)") (class "Default")
      (node (ref "U12") (pin "57") (pinfunction "PD10_57") (pintype "bidirectional"))
    )
    (net (code "119") (name "unconnected-(U12A-PD11-Pad58)") (class "Default")
      (node (ref "U12") (pin "58") (pinfunction "PD11_58") (pintype "bidirectional"))
    )
    (net (code "120") (name "unconnected-(U12B-VBAT-Pad6)") (class "Default")
      (node (ref "U12") (pin "6") (pinfunction "VBAT_6") (pintype "power_in"))
    )
  )
)
